# flyback_circuit.net
KiCad netlist of a schematic drawn in Altium Designer
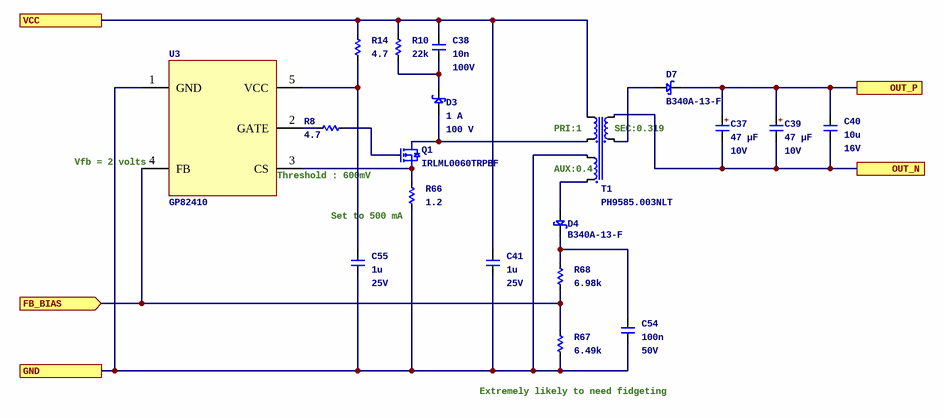
[diagram p0: flyback_circuit.SchDoc]

(export (version "E")
  (design (tool "Eeschema 10.0.6"))
  (components
    (comp (ref "C37")
      (value "TAJB476M010RNJ")
      (footprint "TANT_3.5MMX2.8MMX1.9MM")
      (description "47 µF Molded Tantalum Capacitors 10 V 1411 (3528 Metric), 1210 1Ohm")
      (fields
        (field (name "CAPACITANCE") "47 µF")
        (field (name "MANUFACTURER") "KYOCERA AVX")
        (field (name "VOLTAGE") "10V")
      )
      (libsource (lib "SSCP") (part "CAP_TANT_47UF_10V_TAJB476M010RNJ"))
    )
    (comp (ref "C38")
      (value "CGA3EAC0G2A103JT000E")
      (footprint "C0603")
      (fields
        (field (name "CAPACITANCE") "10n")
        (field (name "MANUFACTURER") "TDK")
        (field (name "VOLTAGE RATING") "100V")
      )
      (libsource (lib "database") (part "__template_cap"))
    )
    (comp (ref "C39")
      (value "TAJB476M010RNJ")
      (footprint "TANT_3.5MMX2.8MMX1.9MM")
      (description "47 µF Molded Tantalum Capacitors 10 V 1411 (3528 Metric), 1210 1Ohm")
      (fields
        (field (name "CAPACITANCE") "47 µF")
        (field (name "MANUFACTURER") "KYOCERA AVX")
        (field (name "VOLTAGE") "10V")
      )
      (libsource (lib "SSCP") (part "CAP_TANT_47UF_10V_TAJB476M010RNJ"))
    )
    (comp (ref "C40")
      (value "CL31B106KOHNNNE")
      (footprint "C1206")
      (fields
        (field (name "CAPACITANCE") "10u")
        (field (name "MANUFACTURER") "Samsung Electro-Mechanics")
        (field (name "VOLTAGE RATING") "16V")
      )
      (libsource (lib "database") (part "__template_cap"))
    )
    (comp (ref "C41")
      (value "CL10B105KA8NNNC")
      (footprint "C0603")
      (fields
        (field (name "CAPACITANCE") "1u")
        (field (name "MANUFACTURER") "Samsung Electro-Mechanics")
        (field (name "VOLTAGE RATING") "25V")
      )
      (libsource (lib "database") (part "__template_cap"))
    )
    (comp (ref "C54")
      (value "CL05B104KB54PNC")
      (footprint "C0402")
      (fields
        (field (name "CAPACITANCE") "100n")
        (field (name "MANUFACTURER") "Samsung Electro-Mechanics")
        (field (name "VOLTAGE RATING") "50V")
      )
      (libsource (lib "database") (part "__template_cap"))
    )
    (comp (ref "C55")
      (value "CL10B105KA8NNNC")
      (footprint "C0603")
      (fields
        (field (name "CAPACITANCE") "1u")
        (field (name "MANUFACTURER") "Samsung Electro-Mechanics")
        (field (name "VOLTAGE RATING") "25V")
      )
      (libsource (lib "database") (part "__template_cap"))
    )
    (comp (ref "D3")
      (value "PMEG10010ELR-QX")
      (footprint "SOD123W")
      (description "DIODE SCHOTTKY 100V 1A SOD123W")
      (fields
        (field (name "MANUFACTURER") "Nexperia")
        (field (name "CURRENT") "1 A")
        (field (name "VOLTAGE") "100 V")
      )
      (libsource (lib "SSCP") (part "SCHOTTKY_100V_PMEG10010ELR-QX"))
    )
    (comp (ref "D4")
      (value "B340A-13-F")
      (footprint "SMA")
      (description "Rectifier Diode, Schottky, 1 Phase, 1 Element, 3A, 40V V(RRM), Silicon")
      (fields (field (name "MANUFACTURER") "Diodes"))
      (libsource (lib "diode") (part "SCHOTTKY_B340A-13-F"))
    )
    (comp (ref "D7")
      (value "B340A-13-F")
      (footprint "SMA")
      (description "Rectifier Diode, Schottky, 1 Phase, 1 Element, 3A, 40V V(RRM), Silicon")
      (fields (field (name "MANUFACTURER") "Diodes"))
      (libsource (lib "diode") (part "SCHOTTKY_B340A-13-F"))
    )
    (comp (ref "Q1")
      (value "IRLML0060TRPBF")
      (footprint "3SOT23")
      (description "N-Channel 60 V 2.7A (Ta) 1.25W (Ta) Surface Mount Micro3™/SOT-23")
      (fields (field (name "MANUFACTURER") "Infineon Technologies"))
      (libsource (lib "SSCP") (part "NFET_60V_IRLML0060TRPBF"))
    )
    (comp (ref "R8")
      (value "4.7")
      (footprint "R0603")
      (fields
        (field (name "MANUFACTURER PART NUMBER") "CRCW06034R70FKEAHP")
        (field (name "MANUFACTURER") "Vishay Intertech")
        (field (name "TOLERANCE") "1%")
      )
      (libsource (lib "database") (part "__template_resistor"))
    )
    (comp (ref "R10")
      (value "22k")
      (footprint "R1206")
      (fields
        (field (name "MANUFACTURER PART NUMBER") "ESR18EZPF2202")
        (field (name "MANUFACTURER") "ROHM Semicon")
        (field (name "TOLERANCE") "1%")
      )
      (libsource (lib "database") (part "__template_resistor"))
    )
    (comp (ref "R14")
      (value "4.7")
      (footprint "R0603")
      (fields
        (field (name "MANUFACTURER PART NUMBER") "CRCW06034R70FKEAHP")
        (field (name "MANUFACTURER") "Vishay Intertech")
        (field (name "TOLERANCE") "1%")
      )
      (libsource (lib "database") (part "__template_resistor"))
    )
    (comp (ref "R66")
      (value "1.2")
      (footprint "R1206")
      (fields
        (field (name "MANUFACTURER PART NUMBER") "HP06W2F120KT5E")
        (field (name "MANUFACTURER") "UNI-ROYAL(Uniroyal Elec)")
        (field (name "TOLERANCE") "1%")
      )
      (libsource (lib "database") (part "__template_resistor"))
    )
    (comp (ref "R67")
      (value "6.49k")
      (footprint "R0402")
      (fields
        (field (name "MANUFACTURER PART NUMBER") "0402WGF6491TCE")
        (field (name "MANUFACTURER") "UNI-ROYAL(Uniroyal Elec)")
        (field (name "TOLERANCE") "1%")
      )
      (libsource (lib "database") (part "__template_resistor"))
    )
    (comp (ref "R68")
      (value "6.98k")
      (footprint "R0402")
      (fields
        (field (name "MANUFACTURER PART NUMBER") "RC0402FR-076K98L")
        (field (name "MANUFACTURER") "YAGEO")
        (field (name "TOLERANCE") "1%")
      )
      (libsource (lib "database") (part "__template_resistor"))
    )
    (comp (ref "T1")
      (value "PH9585.003NLT")
      (footprint "PULSE_PH9585")
      (description "Flyback Converters For SMPS Transformer 2250V Isolation 430kHz Surface Mount")
      (fields (field (name "MANUFACTURER") "Pulse Electronics"))
      (libsource (lib "SSCP") (part "TRANS_PULSE_PH9585.003NLT"))
    )
    (comp (ref "U3")
      (value "GP82410")
      (footprint "5SOT23")
      (description "70kHz 300mV~31V SOT-23-5 AC-DC Controllers and Regulators ROHS\r\nFLYBACK_GP82410")
      (fields (field (name "MANUFACTURER") "Hanrun"))
      (libsource (lib "SSCP") (part "FLYBACK_GP82410"))
    )
  )
  (nets
    (net (code "1") (name "/FB_BIAS") (class "Default")
      (node (ref "R67") (pin "2") (pintype "passive"))
      (node (ref "R68") (pin "1") (pintype "passive"))
      (node (ref "U3") (pin "4") (pinfunction "FB_4") (pintype "passive"))
    )
    (net (code "2") (name "/GND") (class "Default")
      (node (ref "C41") (pin "2") (pintype "passive"))
      (node (ref "C54") (pin "2") (pintype "passive"))
      (node (ref "C55") (pin "2") (pintype "passive"))
      (node (ref "R66") (pin "1") (pintype "passive"))
      (node (ref "R67") (pin "1") (pintype "passive"))
      (node (ref "T1") (pin "3") (pintype "passive"))
      (node (ref "U3") (pin "1") (pinfunction "GND_1") (pintype "passive"))
    )
    (net (code "3") (name "/OUT_N") (class "Default")
      (node (ref "C37") (pin "2") (pintype "passive"))
      (node (ref "C39") (pin "2") (pintype "passive"))
      (node (ref "C40") (pin "2") (pintype "passive"))
      (node (ref "T1") (pin "6") (pintype "passive"))
    )
    (net (code "4") (name "/OUT_P") (class "Default")
      (node (ref "C37") (pin "1") (pintype "passive"))
      (node (ref "C39") (pin "1") (pintype "passive"))
      (node (ref "C40") (pin "1") (pintype "passive"))
      (node (ref "D7") (pin "2") (pintype "passive"))
    )
    (net (code "5") (name "/VCC") (class "Default")
      (node (ref "C38") (pin "1") (pintype "passive"))
      (node (ref "C41") (pin "1") (pintype "passive"))
      (node (ref "R10") (pin "2") (pintype "passive"))
      (node (ref "R14") (pin "1") (pintype "passive"))
      (node (ref "T1") (pin "1") (pintype "passive"))
    )
    (net (code "6") (name "Net-(C38-Pad2)") (class "Default")
      (node (ref "C38") (pin "2") (pintype "passive"))
      (node (ref "D3") (pin "2") (pintype "passive"))
      (node (ref "R10") (pin "1") (pintype "passive"))
    )
    (net (code "7") (name "Net-(C54-Pad1)") (class "Default")
      (node (ref "C54") (pin "1") (pintype "passive"))
      (node (ref "D4") (pin "2") (pintype "passive"))
      (node (ref "R68") (pin "2") (pintype "passive"))
    )
    (net (code "8") (name "Net-(D3-Pad1)") (class "Default")
      (node (ref "D3") (pin "1") (pintype "passive"))
      (node (ref "Q1") (pin "3") (pintype "passive"))
      (node (ref "T1") (pin "2") (pintype "passive"))
    )
    (net (code "9") (name "Net-(D4-Pad1)") (class "Default")
      (node (ref "D4") (pin "1") (pintype "passive"))
      (node (ref "T1") (pin "4") (pintype "passive"))
    )
    (net (code "10") (name "Net-(D7-Pad1)") (class "Default")
      (node (ref "D7") (pin "1") (pintype "passive"))
      (node (ref "T1") (pin "5") (pintype "passive"))
    )
    (net (code "11") (name "Net-(Q1-Pad1)") (class "Default")
      (node (ref "Q1") (pin "1") (pintype "passive"))
      (node (ref "R8") (pin "1") (pintype "passive"))
    )
    (net (code "12") (name "Net-(U3-CS)") (class "Default")
      (node (ref "Q1") (pin "2") (pintype "passive"))
      (node (ref "R66") (pin "2") (pintype "passive"))
      (node (ref "U3") (pin "3") (pinfunction "CS_3") (pintype "passive"))
    )
    (net (code "13") (name "Net-(U3-GATE)") (class "Default")
      (node (ref "R8") (pin "2") (pintype "passive"))
      (node (ref "U3") (pin "2") (pinfunction "GATE_2") (pintype "passive"))
    )
    (net (code "14") (name "Net-(U3-VCC)") (class "Default")
      (node (ref "C55") (pin "1") (pintype "passive"))
      (node (ref "R14") (pin "2") (pintype "passive"))
      (node (ref "U3") (pin "5") (pinfunction "VCC_5") (pintype "passive"))
    )
  )
)
